# COMUNICATE_CON.net
KiCad netlist of a schematic drawn in Altium Designer
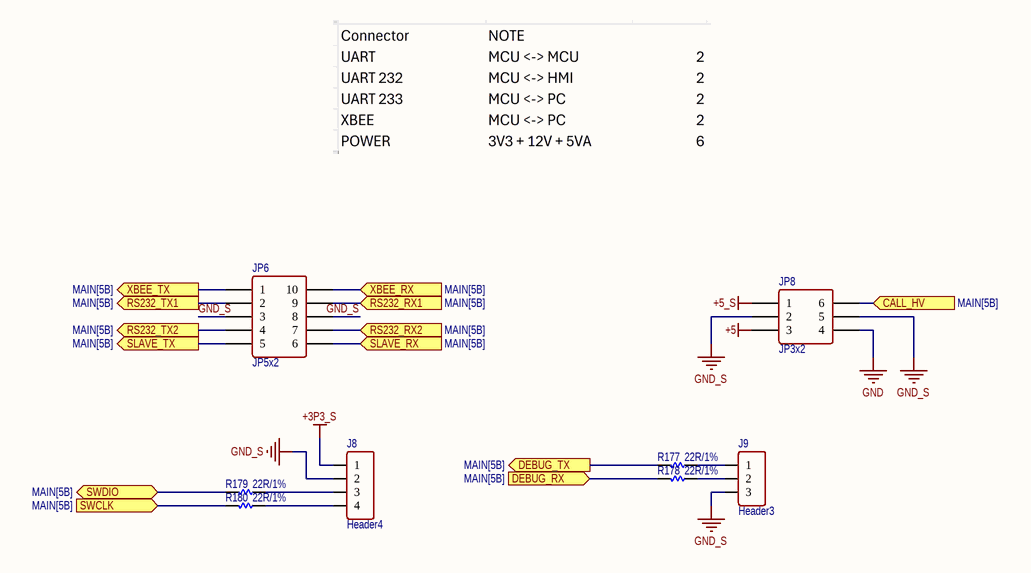
[diagram p0: COMUNICATE_CON.SchDoc]

(export (version "E")
  (design (tool "Eeschema 10.0.6"))
  (components
    (comp (ref "J8")
      (value "Header4")
      (footprint "XH2.54-4-DIP")
      (description "Connector 4")
      (fields
        (field (name "MANUFACTURER") "Würth Elektronik eiSos GmbH")
        (field (name "PARTNO") "613002143121")
        (field (name "CREATED BY") "Karrer Zheng")
      )
      (libsource (lib "Library") (part "Header4"))
    )
    (comp (ref "J9")
      (value "Header3")
      (footprint "XH2.54-3-DIP")
      (description "Connector 3")
      (fields
        (field (name "MANUFACTURER") "Würth Elektronik eiSos GmbH")
        (field (name "PARTNO") "613002143121")
        (field (name "CREATED BY") "Karrer Zheng")
      )
      (libsource (lib "Library") (part "Header3"))
    )
    (comp (ref "JP6")
      (value "JP5x2")
      (footprint "JP5-D2T")
      (description "WR-PHD 2.54 mm Dual Socket Header")
      (fields
        (field (name "MANUFACTURER") "Würth Elektronik eiSos GmbH")
        (field (name "PARTNO") "61301021821")
        (field (name "CREATED BY") "Karrer Zheng")
      )
      (libsource (lib "Library") (part "JP5x2"))
    )
    (comp (ref "JP8")
      (value "JP3x2")
      (footprint "JP3-C2T")
      (description "5-534206-3")
      (fields
        (field (name "MANUFACTURER") "Würth Elektronik eiSos GmbH")
        (field (name "PARTNO") "61300621821")
        (field (name "CREATED BY") "Karrer Zheng")
      )
      (libsource (lib "Library") (part "JP3x2"))
    )
    (comp (ref "R177")
      (value "22R/1%")
      (footprint "RES-SMD-0603")
      (description "ERJ-3EKF22R0V")
      (libsource (lib "Library") (part "Res-SMD"))
    )
    (comp (ref "R178")
      (value "22R/1%")
      (footprint "RES-SMD-0603")
      (description "ERJ-3EKF22R0V")
      (libsource (lib "Library") (part "Res-SMD"))
    )
    (comp (ref "R179")
      (value "22R/1%")
      (footprint "RES-SMD-0603")
      (description "ERJ-3EKF22R0V")
      (libsource (lib "Library") (part "Res-SMD"))
    )
    (comp (ref "R180")
      (value "22R/1%")
      (footprint "RES-SMD-0603")
      (description "ERJ-3EKF22R0V")
      (libsource (lib "Library") (part "Res-SMD"))
    )
  )
  (nets
    (net (code "1") (name "+3P3_S") (class "Default")
      (node (ref "J8") (pin "1") (pinfunction "1_1") (pintype "passive"))
    )
    (net (code "2") (name "+5") (class "Default")
      (node (ref "JP8") (pin "3") (pinfunction "3_3") (pintype "passive"))
    )
    (net (code "3") (name "+5_S") (class "Default")
      (node (ref "JP8") (pin "1") (pinfunction "1_1") (pintype "passive"))
    )
    (net (code "4") (name "/CALL_HV") (class "Default")
      (node (ref "JP8") (pin "6") (pinfunction "6_6") (pintype "passive"))
    )
    (net (code "5") (name "/DEBUG_RX") (class "Default")
      (node (ref "R178") (pin "2") (pinfunction "2_2") (pintype "passive"))
    )
    (net (code "6") (name "/DEBUG_TX") (class "Default")
      (node (ref "R177") (pin "2") (pinfunction "2_2") (pintype "passive"))
    )
    (net (code "7") (name "/RS232_RX1") (class "Default")
      (node (ref "JP6") (pin "9") (pinfunction "9_9") (pintype "passive"))
    )
    (net (code "8") (name "/RS232_RX2") (class "Default")
      (node (ref "JP6") (pin "7") (pinfunction "7_7") (pintype "passive"))
    )
    (net (code "9") (name "/RS232_TX1") (class "Default")
      (node (ref "JP6") (pin "2") (pinfunction "2_2") (pintype "passive"))
    )
    (net (code "10") (name "/RS232_TX2") (class "Default")
      (node (ref "JP6") (pin "4") (pinfunction "4_4") (pintype "passive"))
    )
    (net (code "11") (name "/SLAVE_RX") (class "Default")
      (node (ref "JP6") (pin "6") (pinfunction "6_6") (pintype "passive"))
    )
    (net (code "12") (name "/SLAVE_TX") (class "Default")
      (node (ref "JP6") (pin "5") (pinfunction "5_5") (pintype "passive"))
    )
    (net (code "13") (name "/SWCLK") (class "Default")
      (node (ref "R180") (pin "2") (pinfunction "2_2") (pintype "passive"))
    )
    (net (code "14") (name "/SWDIO") (class "Default")
      (node (ref "R179") (pin "2") (pinfunction "2_2") (pintype "passive"))
    )
    (net (code "15") (name "/XBEE_RX") (class "Default")
      (node (ref "JP6") (pin "10") (pinfunction "10_10") (pintype "passive"))
    )
    (net (code "16") (name "/XBEE_TX") (class "Default")
      (node (ref "JP6") (pin "1") (pinfunction "1_1") (pintype "passive"))
    )
    (net (code "17") (name "GND") (class "Default")
      (node (ref "JP8") (pin "4") (pinfunction "4_4") (pintype "passive"))
    )
    (net (code "18") (name "GND_S") (class "Default")
      (node (ref "J8") (pin "2") (pinfunction "2_2") (pintype "passive"))
      (node (ref "J9") (pin "3") (pinfunction "3_3") (pintype "passive"))
      (node (ref "JP6") (pin "3") (pinfunction "3_3") (pintype "passive"))
      (node (ref "JP6") (pin "8") (pinfunction "8_8") (pintype "passive"))
      (node (ref "JP8") (pin "2") (pinfunction "2_2") (pintype "passive"))
      (node (ref "JP8") (pin "5") (pinfunction "5_5") (pintype "passive"))
    )
    (net (code "19") (name "Net-(J8-Pad3)") (class "Default")
      (node (ref "J8") (pin "3") (pinfunction "3_3") (pintype "passive"))
      (node (ref "R179") (pin "1") (pinfunction "1_1") (pintype "passive"))
    )
    (net (code "20") (name "Net-(J8-Pad4)") (class "Default")
      (node (ref "J8") (pin "4") (pinfunction "4_4") (pintype "passive"))
      (node (ref "R180") (pin "1") (pinfunction "1_1") (pintype "passive"))
    )
    (net (code "21") (name "Net-(J9-Pad1)") (class "Default")
      (node (ref "J9") (pin "1") (pinfunction "1_1") (pintype "passive"))
      (node (ref "R177") (pin "1") (pinfunction "1_1") (pintype "passive"))
    )
    (net (code "22") (name "Net-(J9-Pad2)") (class "Default")
      (node (ref "J9") (pin "2") (pinfunction "2_2") (pintype "passive"))
      (node (ref "R178") (pin "1") (pinfunction "1_1") (pintype "passive"))
    )
  )
)
